# SCH_fuelsensor_2025-04-23.net
KiCad netlist of a schematic drawn in EasyEDA
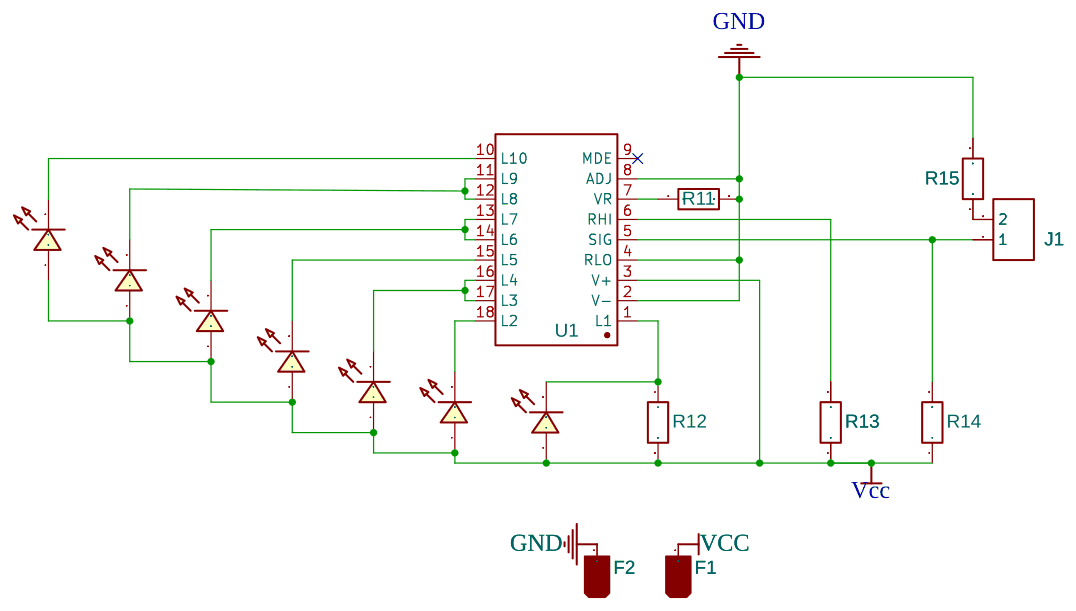
[diagram p0: schematic sheet]

(export (version "E")
  (design (tool "Eeschema 10.0.6"))
  (components
    (comp (ref "F1")
      (value "FASTON-PCB-6.3X0.8")
      (fields
        (field (name "Manufacturer Part") "63849-1")
        (field (name "Manufacturer") "AMP - TE CONNECTIVITY")
      )
      (libsource (lib "") (part "FASTON-PCB-6.3X0.8"))
    )
    (comp (ref "F2")
      (value "FASTON-PCB-6.3X0.8")
      (fields
        (field (name "Manufacturer Part") "63849-1")
        (field (name "Manufacturer") "AMP - TE CONNECTIVITY")
      )
      (libsource (lib "") (part "FASTON-PCB-6.3X0.8"))
    )
    (comp (ref "J1") (value "HDR-M-2.54_1x2") (libsource (lib "") (part "HDR-M-2.54_1x2")))
    (comp (ref "LED11")
      (value "LED-TH-5mm_R")
      (fields
        (field (name "Manufacturer Part") "333-2SURD/S530-A3")
        (field (name "Manufacturer") "EVERLIGHT(台湾亿光)")
      )
      (libsource (lib "") (part "LED-TH-5mm_R"))
    )
    (comp (ref "LED12")
      (value "LED-TH-3mm_R")
      (fields
        (field (name "Manufacturer Part") "204-10SDRD/S530-A3-L")
        (field (name "Manufacturer") "EVERLIGHT(台湾亿光)")
      )
      (libsource (lib "") (part "LED-TH-3mm_R"))
    )
    (comp (ref "LED13")
      (value "LED-TH-3mm_G")
      (fields
        (field (name "Manufacturer Part") "204-10SYGD/S530-E3")
        (field (name "Manufacturer") "EVERLIGHT(台湾亿光)")
      )
      (libsource (lib "") (part "LED-TH-3mm_G"))
    )
    (comp (ref "LED14")
      (value "LED-TH-3mm_G")
      (fields
        (field (name "Manufacturer Part") "204-10SYGD/S530-E3")
        (field (name "Manufacturer") "EVERLIGHT(台湾亿光)")
      )
      (libsource (lib "") (part "LED-TH-3mm_G"))
    )
    (comp (ref "LED15")
      (value "LED-TH-3mm_G")
      (fields
        (field (name "Manufacturer Part") "204-10SYGD/S530-E3")
        (field (name "Manufacturer") "EVERLIGHT(台湾亿光)")
      )
      (libsource (lib "") (part "LED-TH-3mm_G"))
    )
    (comp (ref "LED16")
      (value "LED-TH-3mm_G")
      (fields
        (field (name "Manufacturer Part") "204-10SYGD/S530-E3")
        (field (name "Manufacturer") "EVERLIGHT(台湾亿光)")
      )
      (libsource (lib "") (part "LED-TH-3mm_G"))
    )
    (comp (ref "LED17")
      (value "LED-TH-3mm_G")
      (fields
        (field (name "Manufacturer Part") "204-10SYGD/S530-E3")
        (field (name "Manufacturer") "EVERLIGHT(台湾亿光)")
      )
      (libsource (lib "") (part "LED-TH-3mm_G"))
    )
    (comp (ref "R11") (value "1K") (libsource (lib "") (part "R_AXIAL-0.4_EU_1")))
    (comp (ref "R12") (value "4k7") (libsource (lib "") (part "R_AXIAL-0.4_EU")))
    (comp (ref "R13") (value "33k") (libsource (lib "") (part "R_AXIAL-0.4_EU_2")))
    (comp (ref "R14") (value "680") (libsource (lib "") (part "R_AXIAL-0.3_EU")))
    (comp (ref "R15") (value "15") (libsource (lib "") (part "R_AXIAL-0.3_EU")))
    (comp (ref "U1")
      (value "LM3914N-1/NOPB")
      (fields (field (name "Manufacturer") "TI"))
      (libsource (lib "") (part "LM3914N-1/NOPB"))
    )
  )
  (nets
    (net (code "1") (name "GND") (class "Default")
      (node (ref "F2") (pin "1") (pinfunction "1_1") (pintype "unspecified"))
      (node (ref "R11") (pin "2") (pinfunction "2_2") (pintype "unspecified"))
      (node (ref "R15") (pin "2") (pinfunction "2_2") (pintype "unspecified"))
      (node (ref "U1") (pin "2") (pinfunction "V-_2") (pintype "unspecified"))
      (node (ref "U1") (pin "4") (pinfunction "RLO_4") (pintype "unspecified"))
      (node (ref "U1") (pin "8") (pinfunction "ADJ_8") (pintype "unspecified"))
    )
    (net (code "2") (name "Net-(J1-Pad2)") (class "Default")
      (node (ref "J1") (pin "2") (pinfunction "2_2") (pintype "unspecified"))
      (node (ref "R15") (pin "1") (pinfunction "1_1") (pintype "unspecified"))
    )
    (net (code "3") (name "Net-(U1-L1)") (class "Default")
      (node (ref "LED11") (pin "2") (pinfunction "2_2") (pintype "unspecified"))
      (node (ref "R12") (pin "1") (pinfunction "1_1") (pintype "unspecified"))
      (node (ref "U1") (pin "1") (pinfunction "L1_1") (pintype "unspecified"))
    )
    (net (code "4") (name "Net-(U1-L2)") (class "Default")
      (node (ref "LED12") (pin "2") (pinfunction "2_2") (pintype "unspecified"))
      (node (ref "U1") (pin "18") (pinfunction "L2_18") (pintype "unspecified"))
    )
    (net (code "5") (name "Net-(U1-L3)") (class "Default")
      (node (ref "LED13") (pin "2") (pinfunction "2_2") (pintype "unspecified"))
      (node (ref "U1") (pin "16") (pinfunction "L4_16") (pintype "unspecified"))
      (node (ref "U1") (pin "17") (pinfunction "L3_17") (pintype "unspecified"))
    )
    (net (code "6") (name "Net-(U1-L5)") (class "Default")
      (node (ref "LED14") (pin "2") (pinfunction "2_2") (pintype "unspecified"))
      (node (ref "U1") (pin "15") (pinfunction "L5_15") (pintype "unspecified"))
    )
    (net (code "7") (name "Net-(U1-L6)") (class "Default")
      (node (ref "LED15") (pin "2") (pinfunction "2_2") (pintype "unspecified"))
      (node (ref "U1") (pin "13") (pinfunction "L7_13") (pintype "unspecified"))
      (node (ref "U1") (pin "14") (pinfunction "L6_14") (pintype "unspecified"))
    )
    (net (code "8") (name "Net-(U1-L8)") (class "Default")
      (node (ref "LED16") (pin "2") (pinfunction "2_2") (pintype "unspecified"))
      (node (ref "U1") (pin "11") (pinfunction "L9_11") (pintype "unspecified"))
      (node (ref "U1") (pin "12") (pinfunction "L8_12") (pintype "unspecified"))
    )
    (net (code "9") (name "Net-(U1-L10)") (class "Default")
      (node (ref "LED17") (pin "2") (pinfunction "2_2") (pintype "unspecified"))
      (node (ref "U1") (pin "10") (pinfunction "L10_10") (pintype "unspecified"))
    )
    (net (code "10") (name "Net-(U1-RHI)") (class "Default")
      (node (ref "R13") (pin "2") (pinfunction "2_2") (pintype "unspecified"))
      (node (ref "U1") (pin "6") (pinfunction "RHI_6") (pintype "unspecified"))
    )
    (net (code "11") (name "Net-(U1-SIG)") (class "Default")
      (node (ref "J1") (pin "1") (pinfunction "1_1") (pintype "unspecified"))
      (node (ref "R14") (pin "2") (pinfunction "2_2") (pintype "unspecified"))
      (node (ref "U1") (pin "5") (pinfunction "SIG_5") (pintype "unspecified"))
    )
    (net (code "12") (name "Net-(U1-VR)") (class "Default")
      (node (ref "R11") (pin "1") (pinfunction "1_1") (pintype "unspecified"))
      (node (ref "U1") (pin "7") (pinfunction "VR_7") (pintype "unspecified"))
    )
    (net (code "13") (name "VCC") (class "Default")
      (node (ref "F1") (pin "1") (pinfunction "1_1") (pintype "unspecified"))
    )
    (net (code "14") (name "Vcc") (class "Default")
      (node (ref "LED11") (pin "1") (pinfunction "1_1") (pintype "unspecified"))
      (node (ref "LED12") (pin "1") (pinfunction "1_1") (pintype "unspecified"))
      (node (ref "LED13") (pin "1") (pinfunction "1_1") (pintype "unspecified"))
      (node (ref "LED14") (pin "1") (pinfunction "1_1") (pintype "unspecified"))
      (node (ref "LED15") (pin "1") (pinfunction "1_1") (pintype "unspecified"))
      (node (ref "LED16") (pin "1") (pinfunction "1_1") (pintype "unspecified"))
      (node (ref "LED17") (pin "1") (pinfunction "1_1") (pintype "unspecified"))
      (node (ref "R12") (pin "2") (pinfunction "2_2") (pintype "unspecified"))
      (node (ref "R13") (pin "1") (pinfunction "1_1") (pintype "unspecified"))
      (node (ref "R14") (pin "1") (pinfunction "1_1") (pintype "unspecified"))
      (node (ref "U1") (pin "3") (pinfunction "V+_3") (pintype "unspecified"))
    )
    (net (code "15") (name "unconnected-(U1-MDE-Pad9)") (class "Default")
      (node (ref "U1") (pin "9") (pinfunction "MDE_9") (pintype "unspecified+no_connect"))
    )
  )
)
